# rcps2keyb_v2.net
KiCad netlist of a schematic drawn in EAGLE
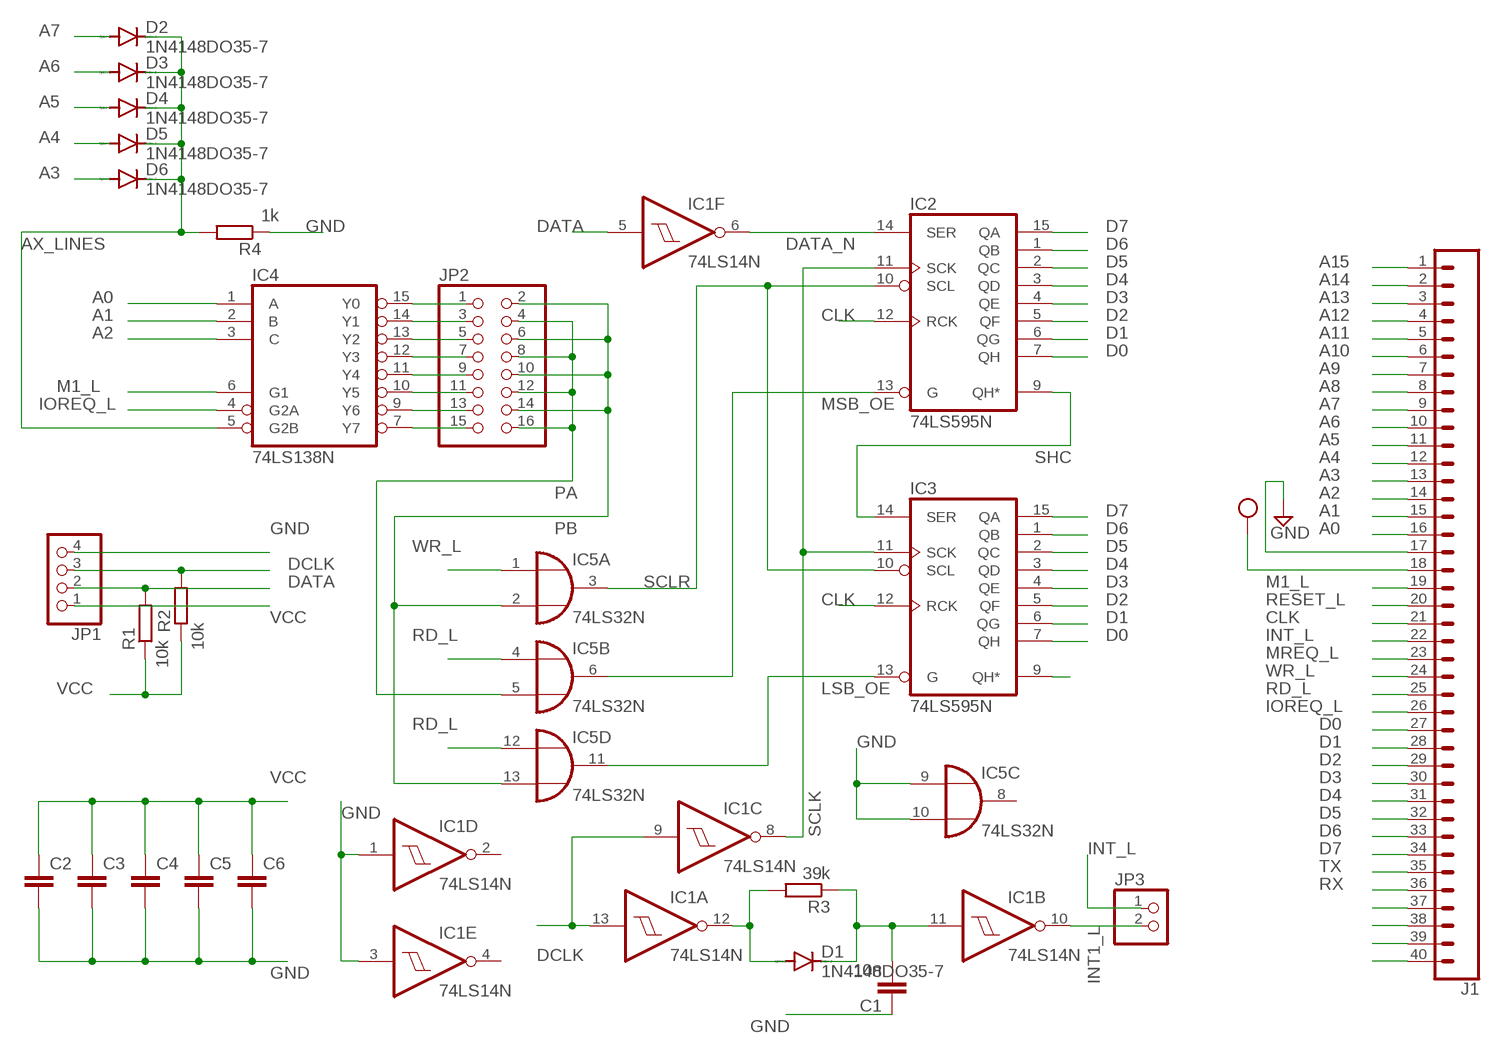
[diagram p0: schematic, sheet 1]

(export (version "E")
  (design (tool "Eeschema 10.0.6"))
  (components
    (comp (ref "C1")
      (value "10n")
      (footprint "eagle-import:C050-025X075")
      (libsource (lib "eagle-import") (part "rcl_334_C-EU050-025X075"))
    )
    (comp (ref "C2")
      (value "C-EU050-025X075")
      (footprint "eagle-import:C050-025X075")
      (libsource (lib "eagle-import") (part "C-EU050-025X075"))
    )
    (comp (ref "C3")
      (value "C-EU050-025X075")
      (footprint "eagle-import:C050-025X075")
      (libsource (lib "eagle-import") (part "C-EU050-025X075"))
    )
    (comp (ref "C4")
      (value "C-EU050-025X075")
      (footprint "eagle-import:C050-025X075")
      (libsource (lib "eagle-import") (part "C-EU050-025X075"))
    )
    (comp (ref "C5")
      (value "C-EU050-025X075")
      (footprint "eagle-import:C050-025X075")
      (libsource (lib "eagle-import") (part "C-EU050-025X075"))
    )
    (comp (ref "C6")
      (value "C-EU050-025X075")
      (footprint "eagle-import:C050-025X075")
      (libsource (lib "eagle-import") (part "C-EU050-025X075"))
    )
    (comp (ref "D1")
      (value "1N4148DO35-7")
      (footprint "eagle-import:DO35-7")
      (libsource (lib "eagle-import") (part "1N4148DO35-7"))
    )
    (comp (ref "D2")
      (value "1N4148DO35-7")
      (footprint "eagle-import:DO35-7")
      (libsource (lib "eagle-import") (part "1N4148DO35-7"))
    )
    (comp (ref "D3")
      (value "1N4148DO35-7")
      (footprint "eagle-import:DO35-7")
      (libsource (lib "eagle-import") (part "1N4148DO35-7"))
    )
    (comp (ref "D4")
      (value "1N4148DO35-7")
      (footprint "eagle-import:DO35-7")
      (libsource (lib "eagle-import") (part "1N4148DO35-7"))
    )
    (comp (ref "D5")
      (value "1N4148DO35-7")
      (footprint "eagle-import:DO35-7")
      (libsource (lib "eagle-import") (part "1N4148DO35-7"))
    )
    (comp (ref "D6")
      (value "1N4148DO35-7")
      (footprint "eagle-import:DO35-7")
      (libsource (lib "eagle-import") (part "1N4148DO35-7"))
    )
    (comp (ref "IC1")
      (value "74LS14N")
      (footprint "eagle-import:DIL14")
      (libsource (lib "eagle-import") (part "7414NLS"))
    )
    (comp (ref "IC2")
      (value "74LS595N")
      (footprint "eagle-import:DIL16")
      (libsource (lib "eagle-import") (part "74595NLS"))
    )
    (comp (ref "IC3")
      (value "74LS595N")
      (footprint "eagle-import:DIL16")
      (libsource (lib "eagle-import") (part "74595NLS"))
    )
    (comp (ref "IC4")
      (value "74LS138N")
      (footprint "eagle-import:DIL16")
      (libsource (lib "eagle-import") (part "74138NLS"))
    )
    (comp (ref "IC5")
      (value "74LS32N")
      (footprint "eagle-import:DIL14")
      (libsource (lib "eagle-import") (part "7432NLS"))
    )
    (comp (ref "J1")
      (value "CONN_40OFFSET")
      (footprint "eagle-import:1X40_OFFSET")
      (libsource (lib "eagle-import") (part "CONN_40OFFSET"))
    )
    (comp (ref "JP1")
      (value "PINHD-1X4")
      (footprint "eagle-import:1X04")
      (libsource (lib "eagle-import") (part "PINHD-1X4"))
    )
    (comp (ref "JP2")
      (value "PINHD-2X8")
      (footprint "eagle-import:2X08")
      (libsource (lib "eagle-import") (part "PINHD-2X8"))
    )
    (comp (ref "JP3")
      (value "PINHD-1X2")
      (footprint "eagle-import:1X02")
      (libsource (lib "eagle-import") (part "PINHD-1X2"))
    )
    (comp (ref "R1")
      (value "10k")
      (footprint "eagle-import:0204_7")
      (libsource (lib "eagle-import") (part "R-EU_0204/7"))
    )
    (comp (ref "R2")
      (value "10k")
      (footprint "eagle-import:0204_7")
      (libsource (lib "eagle-import") (part "R-EU_0204/7"))
    )
    (comp (ref "R3")
      (value "39k")
      (footprint "eagle-import:0204_7")
      (libsource (lib "eagle-import") (part "R-EU_0204/7"))
    )
    (comp (ref "R4")
      (value "1k")
      (footprint "eagle-import:0204_7")
      (libsource (lib "eagle-import") (part "R-EU_0204/7"))
    )
  )
  (nets
    (net (code "1") (name "/A0") (class "Default")
      (node (ref "IC4") (pin "1") (pinfunction "A_1") (pintype "input"))
      (node (ref "J1") (pin "16") (pinfunction "16_16") (pintype "passive"))
    )
    (net (code "2") (name "/A1") (class "Default")
      (node (ref "IC4") (pin "2") (pinfunction "B_2") (pintype "input"))
      (node (ref "J1") (pin "15") (pinfunction "15_15") (pintype "passive"))
    )
    (net (code "3") (name "/A2") (class "Default")
      (node (ref "IC4") (pin "3") (pinfunction "C_3") (pintype "input"))
      (node (ref "J1") (pin "14") (pinfunction "14_14") (pintype "passive"))
    )
    (net (code "4") (name "/A3") (class "Default")
      (node (ref "D6") (pin "A") (pinfunction "A_A") (pintype "passive"))
      (node (ref "J1") (pin "13") (pinfunction "13_13") (pintype "passive"))
    )
    (net (code "5") (name "/A4") (class "Default")
      (node (ref "D5") (pin "A") (pinfunction "A_A") (pintype "passive"))
      (node (ref "J1") (pin "12") (pinfunction "12_12") (pintype "passive"))
    )
    (net (code "6") (name "/A5") (class "Default")
      (node (ref "D4") (pin "A") (pinfunction "A_A") (pintype "passive"))
      (node (ref "J1") (pin "11") (pinfunction "11_11") (pintype "passive"))
    )
    (net (code "7") (name "/A6") (class "Default")
      (node (ref "D3") (pin "A") (pinfunction "A_A") (pintype "passive"))
      (node (ref "J1") (pin "10") (pinfunction "10_10") (pintype "passive"))
    )
    (net (code "8") (name "/A7") (class "Default")
      (node (ref "D2") (pin "A") (pinfunction "A_A") (pintype "passive"))
      (node (ref "J1") (pin "9") (pinfunction "9_9") (pintype "passive"))
    )
    (net (code "9") (name "/A8") (class "Default")
      (node (ref "J1") (pin "8") (pinfunction "8_8") (pintype "passive"))
    )
    (net (code "10") (name "/A9") (class "Default")
      (node (ref "J1") (pin "7") (pinfunction "7_7") (pintype "passive"))
    )
    (net (code "11") (name "/A10") (class "Default")
      (node (ref "J1") (pin "6") (pinfunction "6_6") (pintype "passive"))
    )
    (net (code "12") (name "/A11") (class "Default")
      (node (ref "J1") (pin "5") (pinfunction "5_5") (pintype "passive"))
    )
    (net (code "13") (name "/A12") (class "Default")
      (node (ref "J1") (pin "4") (pinfunction "4_4") (pintype "passive"))
    )
    (net (code "14") (name "/A13") (class "Default")
      (node (ref "J1") (pin "3") (pinfunction "3_3") (pintype "passive"))
    )
    (net (code "15") (name "/A14") (class "Default")
      (node (ref "J1") (pin "2") (pinfunction "2_2") (pintype "passive"))
    )
    (net (code "16") (name "/A15") (class "Default")
      (node (ref "J1") (pin "1") (pinfunction "1_1") (pintype "passive"))
    )
    (net (code "17") (name "/AX_LINES") (class "Default")
      (node (ref "D2") (pin "C") (pinfunction "C_C") (pintype "passive"))
      (node (ref "D3") (pin "C") (pinfunction "C_C") (pintype "passive"))
      (node (ref "D4") (pin "C") (pinfunction "C_C") (pintype "passive"))
      (node (ref "D5") (pin "C") (pinfunction "C_C") (pintype "passive"))
      (node (ref "D6") (pin "C") (pinfunction "C_C") (pintype "passive"))
      (node (ref "IC4") (pin "5") (pinfunction "G2B_5") (pintype "input"))
      (node (ref "R4") (pin "2") (pinfunction "2_2") (pintype "passive"))
    )
    (net (code "18") (name "/CLK") (class "Default")
      (node (ref "IC2") (pin "12") (pinfunction "RCK_12") (pintype "input"))
      (node (ref "IC3") (pin "12") (pinfunction "RCK_12") (pintype "input"))
      (node (ref "J1") (pin "21") (pinfunction "21_21") (pintype "passive"))
    )
    (net (code "19") (name "/D0") (class "Default")
      (node (ref "IC2") (pin "7") (pinfunction "QH_7") (pintype "tri_state"))
      (node (ref "IC3") (pin "7") (pinfunction "QH_7") (pintype "tri_state"))
      (node (ref "J1") (pin "27") (pinfunction "27_27") (pintype "passive"))
    )
    (net (code "20") (name "/D1") (class "Default")
      (node (ref "IC2") (pin "6") (pinfunction "QG_6") (pintype "tri_state"))
      (node (ref "IC3") (pin "6") (pinfunction "QG_6") (pintype "tri_state"))
      (node (ref "J1") (pin "28") (pinfunction "28_28") (pintype "passive"))
    )
    (net (code "21") (name "/D2") (class "Default")
      (node (ref "IC2") (pin "5") (pinfunction "QF_5") (pintype "tri_state"))
      (node (ref "IC3") (pin "5") (pinfunction "QF_5") (pintype "tri_state"))
      (node (ref "J1") (pin "29") (pinfunction "29_29") (pintype "passive"))
    )
    (net (code "22") (name "/D3") (class "Default")
      (node (ref "IC2") (pin "4") (pinfunction "QE_4") (pintype "tri_state"))
      (node (ref "IC3") (pin "4") (pinfunction "QE_4") (pintype "tri_state"))
      (node (ref "J1") (pin "30") (pinfunction "30_30") (pintype "passive"))
    )
    (net (code "23") (name "/D4") (class "Default")
      (node (ref "IC2") (pin "3") (pinfunction "QD_3") (pintype "tri_state"))
      (node (ref "IC3") (pin "3") (pinfunction "QD_3") (pintype "tri_state"))
      (node (ref "J1") (pin "31") (pinfunction "31_31") (pintype "passive"))
    )
    (net (code "24") (name "/D5") (class "Default")
      (node (ref "IC2") (pin "2") (pinfunction "QC_2") (pintype "tri_state"))
      (node (ref "IC3") (pin "2") (pinfunction "QC_2") (pintype "tri_state"))
      (node (ref "J1") (pin "32") (pinfunction "32_32") (pintype "passive"))
    )
    (net (code "25") (name "/D6") (class "Default")
      (node (ref "IC2") (pin "1") (pinfunction "QB_1") (pintype "tri_state"))
      (node (ref "IC3") (pin "1") (pinfunction "QB_1") (pintype "tri_state"))
      (node (ref "J1") (pin "33") (pinfunction "33_33") (pintype "passive"))
    )
    (net (code "26") (name "/D7") (class "Default")
      (node (ref "IC2") (pin "15") (pinfunction "QA_15") (pintype "tri_state"))
      (node (ref "IC3") (pin "15") (pinfunction "QA_15") (pintype "tri_state"))
      (node (ref "J1") (pin "34") (pinfunction "34_34") (pintype "passive"))
    )
    (net (code "27") (name "/DATA") (class "Default")
      (node (ref "IC1") (pin "5") (pinfunction "I_5") (pintype "input"))
      (node (ref "JP1") (pin "2") (pinfunction "2_2") (pintype "passive"))
      (node (ref "R1") (pin "2") (pinfunction "2_2") (pintype "passive"))
    )
    (net (code "28") (name "/DATA_N") (class "Default")
      (node (ref "IC1") (pin "6") (pinfunction "O_6") (pintype "output"))
      (node (ref "IC2") (pin "14") (pinfunction "SER_14") (pintype "input"))
    )
    (net (code "29") (name "/DCLK") (class "Default")
      (node (ref "IC1") (pin "13") (pinfunction "I_13") (pintype "input"))
      (node (ref "IC1") (pin "9") (pinfunction "I_9") (pintype "input"))
      (node (ref "JP1") (pin "3") (pinfunction "3_3") (pintype "passive"))
      (node (ref "R2") (pin "2") (pinfunction "2_2") (pintype "passive"))
    )
    (net (code "30") (name "/INT1_L") (class "Default")
      (node (ref "IC1") (pin "10") (pinfunction "O_10") (pintype "output"))
      (node (ref "JP3") (pin "2") (pinfunction "2_2") (pintype "passive"))
    )
    (net (code "31") (name "/INT_L") (class "Default")
      (node (ref "J1") (pin "22") (pinfunction "22_22") (pintype "passive"))
      (node (ref "JP3") (pin "1") (pinfunction "1_1") (pintype "passive"))
    )
    (net (code "32") (name "/IOREQ_L") (class "Default")
      (node (ref "IC4") (pin "4") (pinfunction "G2A_4") (pintype "input"))
      (node (ref "J1") (pin "26") (pinfunction "26_26") (pintype "passive"))
    )
    (net (code "33") (name "/LSB_OE") (class "Default")
      (node (ref "IC3") (pin "13") (pinfunction "G_13") (pintype "input"))
      (node (ref "IC5") (pin "11") (pinfunction "O_11") (pintype "output"))
    )
    (net (code "34") (name "/M1_L") (class "Default")
      (node (ref "IC4") (pin "6") (pinfunction "G1_6") (pintype "input"))
      (node (ref "J1") (pin "19") (pinfunction "19_19") (pintype "passive"))
    )
    (net (code "35") (name "/MREQ_L") (class "Default")
      (node (ref "J1") (pin "23") (pinfunction "23_23") (pintype "passive"))
    )
    (net (code "36") (name "/MSB_OE") (class "Default")
      (node (ref "IC2") (pin "13") (pinfunction "G_13") (pintype "input"))
      (node (ref "IC5") (pin "6") (pinfunction "O_6") (pintype "output"))
    )
    (net (code "37") (name "/PA") (class "Default")
      (node (ref "IC5") (pin "5") (pinfunction "I1_5") (pintype "input"))
      (node (ref "JP2") (pin "12") (pinfunction "12_12") (pintype "passive"))
      (node (ref "JP2") (pin "16") (pinfunction "16_16") (pintype "passive"))
      (node (ref "JP2") (pin "4") (pinfunction "4_4") (pintype "passive"))
      (node (ref "JP2") (pin "8") (pinfunction "8_8") (pintype "passive"))
    )
    (net (code "38") (name "/PB") (class "Default")
      (node (ref "IC5") (pin "13") (pinfunction "I1_13") (pintype "input"))
      (node (ref "IC5") (pin "2") (pinfunction "I1_2") (pintype "input"))
      (node (ref "JP2") (pin "10") (pinfunction "10_10") (pintype "passive"))
      (node (ref "JP2") (pin "14") (pinfunction "14_14") (pintype "passive"))
      (node (ref "JP2") (pin "2") (pinfunction "2_2") (pintype "passive"))
      (node (ref "JP2") (pin "6") (pinfunction "6_6") (pintype "passive"))
    )
    (net (code "39") (name "/RD_L") (class "Default")
      (node (ref "IC5") (pin "12") (pinfunction "I0_12") (pintype "input"))
      (node (ref "IC5") (pin "4") (pinfunction "I0_4") (pintype "input"))
      (node (ref "J1") (pin "25") (pinfunction "25_25") (pintype "passive"))
    )
    (net (code "40") (name "/RESET_L") (class "Default")
      (node (ref "J1") (pin "20") (pinfunction "20_20") (pintype "passive"))
    )
    (net (code "41") (name "/RX") (class "Default")
      (node (ref "J1") (pin "36") (pinfunction "36_36") (pintype "passive"))
    )
    (net (code "42") (name "/SCLK") (class "Default")
      (node (ref "IC1") (pin "8") (pinfunction "O_8") (pintype "output"))
      (node (ref "IC2") (pin "11") (pinfunction "SCK_11") (pintype "input"))
      (node (ref "IC3") (pin "11") (pinfunction "SCK_11") (pintype "input"))
    )
    (net (code "43") (name "/SCLR") (class "Default")
      (node (ref "IC2") (pin "10") (pinfunction "SCL_10") (pintype "input"))
      (node (ref "IC3") (pin "10") (pinfunction "SCL_10") (pintype "input"))
      (node (ref "IC5") (pin "3") (pinfunction "O_3") (pintype "output"))
    )
    (net (code "44") (name "/SHC") (class "Default")
      (node (ref "IC2") (pin "9") (pinfunction "QH*_9") (pintype "tri_state"))
      (node (ref "IC3") (pin "14") (pinfunction "SER_14") (pintype "input"))
    )
    (net (code "45") (name "/TX") (class "Default")
      (node (ref "J1") (pin "35") (pinfunction "35_35") (pintype "passive"))
    )
    (net (code "46") (name "/WR_L") (class "Default")
      (node (ref "IC5") (pin "1") (pinfunction "I0_1") (pintype "input"))
      (node (ref "J1") (pin "24") (pinfunction "24_24") (pintype "passive"))
    )
    (net (code "47") (name "GND") (class "Default")
      (node (ref "C1") (pin "1") (pinfunction "1_1") (pintype "passive"))
      (node (ref "C2") (pin "2") (pinfunction "2_2") (pintype "passive"))
      (node (ref "C3") (pin "2") (pinfunction "2_2") (pintype "passive"))
      (node (ref "C4") (pin "2") (pinfunction "2_2") (pintype "passive"))
      (node (ref "C5") (pin "2") (pinfunction "2_2") (pintype "passive"))
      (node (ref "C6") (pin "2") (pinfunction "2_2") (pintype "passive"))
      (node (ref "IC1") (pin "1") (pinfunction "I_1") (pintype "input"))
      (node (ref "IC1") (pin "3") (pinfunction "I_3") (pintype "input"))
      (node (ref "IC5") (pin "10") (pinfunction "I1_10") (pintype "input"))
      (node (ref "IC5") (pin "9") (pinfunction "I0_9") (pintype "input"))
      (node (ref "J1") (pin "17") (pinfunction "17_17") (pintype "passive"))
      (node (ref "JP1") (pin "4") (pinfunction "4_4") (pintype "passive"))
      (node (ref "R4") (pin "1") (pinfunction "1_1") (pintype "passive"))
    )
    (net (code "48") (name "Net-(IC1A-O)") (class "Default")
      (node (ref "D1") (pin "A") (pinfunction "A_A") (pintype "passive"))
      (node (ref "IC1") (pin "12") (pinfunction "O_12") (pintype "output"))
      (node (ref "R3") (pin "2") (pinfunction "2_2") (pintype "passive"))
    )
    (net (code "49") (name "Net-(IC1B-I)") (class "Default")
      (node (ref "C1") (pin "2") (pinfunction "2_2") (pintype "passive"))
      (node (ref "D1") (pin "C") (pinfunction "C_C") (pintype "passive"))
      (node (ref "IC1") (pin "11") (pinfunction "I_11") (pintype "input"))
      (node (ref "R3") (pin "1") (pinfunction "1_1") (pintype "passive"))
    )
    (net (code "50") (name "Net-(IC4A-Y0)") (class "Default")
      (node (ref "IC4") (pin "15") (pinfunction "Y0_15") (pintype "output"))
      (node (ref "JP2") (pin "1") (pinfunction "1_1") (pintype "passive"))
    )
    (net (code "51") (name "Net-(IC4A-Y1)") (class "Default")
      (node (ref "IC4") (pin "14") (pinfunction "Y1_14") (pintype "output"))
      (node (ref "JP2") (pin "3") (pinfunction "3_3") (pintype "passive"))
    )
    (net (code "52") (name "Net-(IC4A-Y2)") (class "Default")
      (node (ref "IC4") (pin "13") (pinfunction "Y2_13") (pintype "output"))
      (node (ref "JP2") (pin "5") (pinfunction "5_5") (pintype "passive"))
    )
    (net (code "53") (name "Net-(IC4A-Y3)") (class "Default")
      (node (ref "IC4") (pin "12") (pinfunction "Y3_12") (pintype "output"))
      (node (ref "JP2") (pin "7") (pinfunction "7_7") (pintype "passive"))
    )
    (net (code "54") (name "Net-(IC4A-Y4)") (class "Default")
      (node (ref "IC4") (pin "11") (pinfunction "Y4_11") (pintype "output"))
      (node (ref "JP2") (pin "9") (pinfunction "9_9") (pintype "passive"))
    )
    (net (code "55") (name "Net-(IC4A-Y5)") (class "Default")
      (node (ref "IC4") (pin "10") (pinfunction "Y5_10") (pintype "output"))
      (node (ref "JP2") (pin "11") (pinfunction "11_11") (pintype "passive"))
    )
    (net (code "56") (name "Net-(IC4A-Y6)") (class "Default")
      (node (ref "IC4") (pin "9") (pinfunction "Y6_9") (pintype "output"))
      (node (ref "JP2") (pin "13") (pinfunction "13_13") (pintype "passive"))
    )
    (net (code "57") (name "Net-(IC4A-Y7)") (class "Default")
      (node (ref "IC4") (pin "7") (pinfunction "Y7_7") (pintype "output"))
      (node (ref "JP2") (pin "15") (pinfunction "15_15") (pintype "passive"))
    )
    (net (code "58") (name "VCC") (class "Default")
      (node (ref "C2") (pin "1") (pinfunction "1_1") (pintype "passive"))
      (node (ref "C3") (pin "1") (pinfunction "1_1") (pintype "passive"))
      (node (ref "C4") (pin "1") (pinfunction "1_1") (pintype "passive"))
      (node (ref "C5") (pin "1") (pinfunction "1_1") (pintype "passive"))
      (node (ref "C6") (pin "1") (pinfunction "1_1") (pintype "passive"))
      (node (ref "J1") (pin "18") (pinfunction "18_18") (pintype "passive"))
      (node (ref "JP1") (pin "1") (pinfunction "1_1") (pintype "passive"))
      (node (ref "R1") (pin "1") (pinfunction "1_1") (pintype "passive"))
      (node (ref "R2") (pin "1") (pinfunction "1_1") (pintype "passive"))
    )
    (net (code "59") (name "unconnected-(IC1D-O-Pad2)") (class "Default")
      (node (ref "IC1") (pin "2") (pinfunction "O_2") (pintype "output"))
    )
    (net (code "60") (name "unconnected-(IC1E-O-Pad4)") (class "Default")
      (node (ref "IC1") (pin "4") (pinfunction "O_4") (pintype "output"))
    )
    (net (code "61") (name "unconnected-(IC3A-QH*-Pad9)") (class "Default")
      (node (ref "IC3") (pin "9") (pinfunction "QH*_9") (pintype "tri_state"))
    )
    (net (code "62") (name "unconnected-(IC5C-O-Pad8)") (class "Default")
      (node (ref "IC5") (pin "8") (pinfunction "O_8") (pintype "output"))
    )
    (net (code "63") (name "unconnected-(J1-Pad37)") (class "Default")
      (node (ref "J1") (pin "37") (pinfunction "37_37") (pintype "passive"))
    )
    (net (code "64") (name "unconnected-(J1-Pad38)") (class "Default")
      (node (ref "J1") (pin "38") (pinfunction "38_38") (pintype "passive"))
    )
    (net (code "65") (name "unconnected-(J1-Pad39)") (class "Default")
      (node (ref "J1") (pin "39") (pinfunction "39_39") (pintype "passive"))
    )
    (net (code "66") (name "unconnected-(J1-Pad40)") (class "Default")
      (node (ref "J1") (pin "40") (pinfunction "40_40") (pintype "passive"))
    )
  )
)
